# V1.net
KiCad netlist of a schematic drawn in Altium Designer
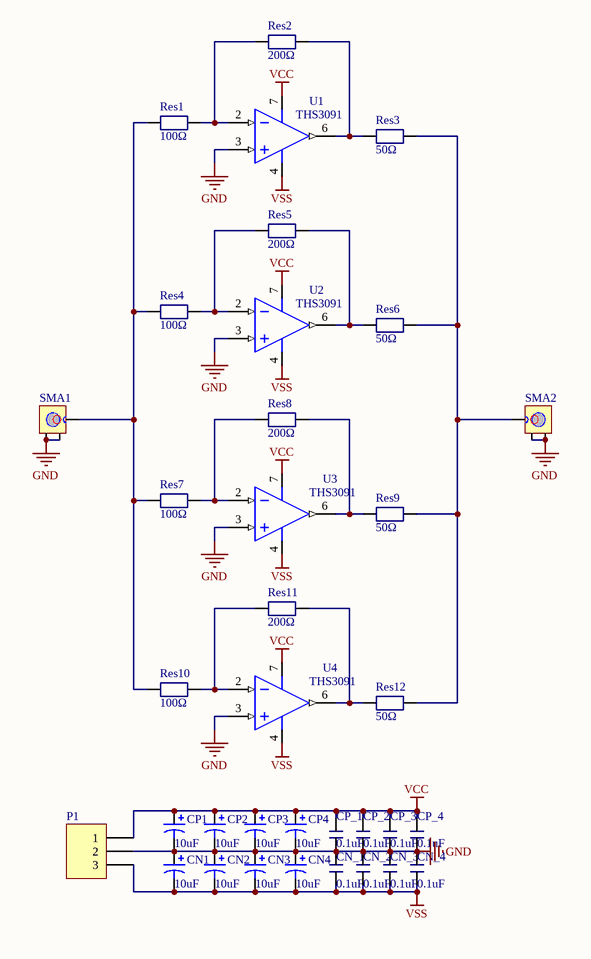
[diagram p0: V1.SchDoc]

(export (version "E")
  (design (tool "Eeschema 10.0.6"))
  (components
    (comp (ref "CN1")
      (value "10uF")
      (footprint "CAP_BTAN")
      (description "Polarized Capacitor (Radial)")
      (fields (field (name "Comment") "Cap Pol1") (field (name "PUBLISHER") "Altium Limited"))
      (libsource (lib "Miscellaneous Devices") (part "Cap Pol1"))
    )
    (comp (ref "CN2")
      (value "10uF")
      (footprint "CAP_BTAN")
      (description "Polarized Capacitor (Radial)")
      (fields (field (name "Comment") "Cap Pol1") (field (name "PUBLISHER") "Altium Limited"))
      (libsource (lib "Miscellaneous Devices") (part "Cap Pol1"))
    )
    (comp (ref "CN3")
      (value "10uF")
      (footprint "CAP_BTAN")
      (description "Polarized Capacitor (Radial)")
      (fields (field (name "Comment") "Cap Pol1") (field (name "PUBLISHER") "Altium Limited"))
      (libsource (lib "Miscellaneous Devices") (part "Cap Pol1"))
    )
    (comp (ref "CN4")
      (value "10uF")
      (footprint "CAP_BTAN")
      (description "Polarized Capacitor (Radial)")
      (fields (field (name "Comment") "Cap Pol1") (field (name "PUBLISHER") "Altium Limited"))
      (libsource (lib "Miscellaneous Devices") (part "Cap Pol1"))
    )
    (comp (ref "CN_1")
      (value "0.1uF")
      (footprint "C0805")
      (description "贴片电容")
      (fields (field (name "Comment") "cap"))
      (libsource (lib "Fengyie") (part "cap"))
    )
    (comp (ref "CN_2")
      (value "0.1uF")
      (footprint "C0805")
      (description "贴片电容")
      (fields (field (name "Comment") "cap"))
      (libsource (lib "Fengyie") (part "cap"))
    )
    (comp (ref "CN_3")
      (value "0.1uF")
      (footprint "C0805")
      (description "贴片电容")
      (fields (field (name "Comment") "cap"))
      (libsource (lib "Fengyie") (part "cap"))
    )
    (comp (ref "CN_4")
      (value "0.1uF")
      (footprint "C0805")
      (description "贴片电容")
      (fields (field (name "Comment") "cap"))
      (libsource (lib "Fengyie") (part "cap"))
    )
    (comp (ref "CP1")
      (value "10uF")
      (footprint "CAP_BTAN")
      (description "Polarized Capacitor (Radial)")
      (fields (field (name "Comment") "Cap Pol1") (field (name "PUBLISHER") "Altium Limited"))
      (libsource (lib "Miscellaneous Devices") (part "Cap Pol1"))
    )
    (comp (ref "CP2")
      (value "10uF")
      (footprint "CAP_BTAN")
      (description "Polarized Capacitor (Radial)")
      (fields (field (name "Comment") "Cap Pol1") (field (name "PUBLISHER") "Altium Limited"))
      (libsource (lib "Miscellaneous Devices") (part "Cap Pol1"))
    )
    (comp (ref "CP3")
      (value "10uF")
      (footprint "CAP_BTAN")
      (description "Polarized Capacitor (Radial)")
      (fields (field (name "Comment") "Cap Pol1") (field (name "PUBLISHER") "Altium Limited"))
      (libsource (lib "Miscellaneous Devices") (part "Cap Pol1"))
    )
    (comp (ref "CP4")
      (value "10uF")
      (footprint "CAP_BTAN")
      (description "Polarized Capacitor (Radial)")
      (fields (field (name "Comment") "Cap Pol1") (field (name "PUBLISHER") "Altium Limited"))
      (libsource (lib "Miscellaneous Devices") (part "Cap Pol1"))
    )
    (comp (ref "CP_1")
      (value "0.1uF")
      (footprint "C0805")
      (description "贴片电容")
      (fields (field (name "Comment") "cap"))
      (libsource (lib "Fengyie") (part "cap"))
    )
    (comp (ref "CP_2")
      (value "0.1uF")
      (footprint "C0805")
      (description "贴片电容")
      (fields (field (name "Comment") "cap"))
      (libsource (lib "Fengyie") (part "cap"))
    )
    (comp (ref "CP_3")
      (value "0.1uF")
      (footprint "C0805")
      (description "贴片电容")
      (fields (field (name "Comment") "cap"))
      (libsource (lib "Fengyie") (part "cap"))
    )
    (comp (ref "CP_4")
      (value "0.1uF")
      (footprint "C0805")
      (description "贴片电容")
      (fields (field (name "Comment") "cap"))
      (libsource (lib "Fengyie") (part "cap"))
    )
    (comp (ref "P1")
      (value "Header 3")
      (footprint "HDR1X3")
      (description "Header, 3-Pin")
      (fields (field (name "PUBLISHER") "Altium Limited"))
      (libsource (lib "Miscellaneous Connectors") (part "Header 3"))
    )
    (comp (ref "Res1")
      (value "100Ω")
      (footprint "C0805")
      (description "适用于0805的贴片元件，包括磁珠")
      (fields (field (name "Comment") "Res"))
      (libsource (lib "Fengyie") (part "Res"))
    )
    (comp (ref "Res2")
      (value "200Ω")
      (footprint "R-AXIAL0.3")
      (description "适用于0805的贴片元件，包括磁珠")
      (fields (field (name "Comment") "Res"))
      (libsource (lib "Fengyie") (part "Res"))
    )
    (comp (ref "Res3")
      (value "50Ω")
      (footprint "C0805")
      (description "适用于0805的贴片元件，包括磁珠")
      (fields (field (name "Comment") "Res"))
      (libsource (lib "Fengyie") (part "Res"))
    )
    (comp (ref "Res4")
      (value "100Ω")
      (footprint "C0805")
      (description "适用于0805的贴片元件，包括磁珠")
      (fields (field (name "Comment") "Res"))
      (libsource (lib "Fengyie") (part "Res"))
    )
    (comp (ref "Res5")
      (value "200Ω")
      (footprint "R-AXIAL0.3")
      (description "适用于0805的贴片元件，包括磁珠")
      (fields (field (name "Comment") "Res"))
      (libsource (lib "Fengyie") (part "Res"))
    )
    (comp (ref "Res6")
      (value "50Ω")
      (footprint "C0805")
      (description "适用于0805的贴片元件，包括磁珠")
      (fields (field (name "Comment") "Res"))
      (libsource (lib "Fengyie") (part "Res"))
    )
    (comp (ref "Res7")
      (value "100Ω")
      (footprint "C0805")
      (description "适用于0805的贴片元件，包括磁珠")
      (fields (field (name "Comment") "Res"))
      (libsource (lib "Fengyie") (part "Res"))
    )
    (comp (ref "Res8")
      (value "200Ω")
      (footprint "R-AXIAL0.3")
      (description "适用于0805的贴片元件，包括磁珠")
      (fields (field (name "Comment") "Res"))
      (libsource (lib "Fengyie") (part "Res"))
    )
    (comp (ref "Res9")
      (value "50Ω")
      (footprint "C0805")
      (description "适用于0805的贴片元件，包括磁珠")
      (fields (field (name "Comment") "Res"))
      (libsource (lib "Fengyie") (part "Res"))
    )
    (comp (ref "Res10")
      (value "100Ω")
      (footprint "C0805")
      (description "适用于0805的贴片元件，包括磁珠")
      (fields (field (name "Comment") "Res"))
      (libsource (lib "Fengyie") (part "Res"))
    )
    (comp (ref "Res11")
      (value "200Ω")
      (footprint "R-AXIAL0.3")
      (description "适用于0805的贴片元件，包括磁珠")
      (fields (field (name "Comment") "Res"))
      (libsource (lib "Fengyie") (part "Res"))
    )
    (comp (ref "Res12")
      (value "50Ω")
      (footprint "C0805")
      (description "适用于0805的贴片元件，包括磁珠")
      (fields (field (name "Comment") "Res"))
      (libsource (lib "Fengyie") (part "Res"))
    )
    (comp (ref "SMA1")
      (value "SMA-xie")
      (footprint "sma-xie")
      (description "外螺内孔，斜角，或直四角斜着放置")
      (libsource (lib "Fengyie") (part "SMA-xie"))
    )
    (comp (ref "SMA2")
      (value "SMA-xie")
      (footprint "sma-xie")
      (description "外螺内孔，斜角，或直四角斜着放置")
      (libsource (lib "") (part "SMA-xie_1"))
    )
    (comp (ref "U1")
      (value "THS3091")
      (footprint "SOIC-8D")
      (description "单路高压低失真电流反馈 运放 ,通常申请DDA，即下方带有热焊盘的，有利于散热")
      (libsource (lib "Fengyie") (part "THS3091"))
    )
    (comp (ref "U2")
      (value "THS3091")
      (footprint "SOIC-8D")
      (description "单路高压低失真电流反馈 运放 ,通常申请DDA，即下方带有热焊盘的，有利于散热")
      (libsource (lib "Fengyie") (part "THS3091"))
    )
    (comp (ref "U3")
      (value "THS3091")
      (footprint "SOIC-8D")
      (description "单路高压低失真电流反馈 运放 ,通常申请DDA，即下方带有热焊盘的，有利于散热")
      (libsource (lib "Fengyie") (part "THS3091"))
    )
    (comp (ref "U4")
      (value "THS3091")
      (footprint "SOIC-8D")
      (description "单路高压低失真电流反馈 运放 ,通常申请DDA，即下方带有热焊盘的，有利于散热")
      (libsource (lib "Fengyie") (part "THS3091"))
    )
  )
  (nets
    (net (code "1") (name "GND") (class "Default")
      (node (ref "CN1") (pin "1") (pinfunction "1_1") (pintype "passive"))
      (node (ref "CN2") (pin "1") (pinfunction "1_1") (pintype "passive"))
      (node (ref "CN3") (pin "1") (pinfunction "1_1") (pintype "passive"))
      (node (ref "CN4") (pin "1") (pinfunction "1_1") (pintype "passive"))
      (node (ref "CN_1") (pin "1") (pinfunction "1_1") (pintype "passive"))
      (node (ref "CN_2") (pin "1") (pinfunction "1_1") (pintype "passive"))
      (node (ref "CN_3") (pin "1") (pinfunction "1_1") (pintype "passive"))
      (node (ref "CN_4") (pin "1") (pinfunction "1_1") (pintype "passive"))
      (node (ref "CP1") (pin "2") (pinfunction "2_2") (pintype "passive"))
      (node (ref "CP2") (pin "2") (pinfunction "2_2") (pintype "passive"))
      (node (ref "CP3") (pin "2") (pinfunction "2_2") (pintype "passive"))
      (node (ref "CP4") (pin "2") (pinfunction "2_2") (pintype "passive"))
      (node (ref "CP_1") (pin "2") (pinfunction "2_2") (pintype "passive"))
      (node (ref "CP_2") (pin "2") (pinfunction "2_2") (pintype "passive"))
      (node (ref "CP_3") (pin "2") (pinfunction "2_2") (pintype "passive"))
      (node (ref "CP_4") (pin "2") (pinfunction "2_2") (pintype "passive"))
      (node (ref "P1") (pin "2") (pinfunction "2_2") (pintype "passive"))
      (node (ref "SMA1") (pin "1") (pinfunction "gnd_1") (pintype "passive"))
      (node (ref "SMA1") (pin "3") (pinfunction "gnd_3") (pintype "passive"))
      (node (ref "SMA2") (pin "1") (pinfunction "gnd_1") (pintype "passive"))
      (node (ref "SMA2") (pin "3") (pinfunction "gnd_3") (pintype "passive"))
      (node (ref "U1") (pin "3") (pinfunction "IN+_3") (pintype "input"))
      (node (ref "U2") (pin "3") (pinfunction "IN+_3") (pintype "input"))
      (node (ref "U3") (pin "3") (pinfunction "IN+_3") (pintype "input"))
      (node (ref "U4") (pin "3") (pinfunction "IN+_3") (pintype "input"))
    )
    (net (code "2") (name "Net-(SMA1-signal)") (class "Default")
      (node (ref "Res1") (pin "1") (pinfunction "1_1") (pintype "passive"))
      (node (ref "Res10") (pin "1") (pinfunction "1_1") (pintype "passive"))
      (node (ref "Res4") (pin "1") (pinfunction "1_1") (pintype "passive"))
      (node (ref "Res7") (pin "1") (pinfunction "1_1") (pintype "passive"))
      (node (ref "SMA1") (pin "2") (pinfunction "signal_2") (pintype "passive"))
    )
    (net (code "3") (name "Net-(SMA2-signal)") (class "Default")
      (node (ref "Res12") (pin "2") (pinfunction "2_2") (pintype "passive"))
      (node (ref "Res3") (pin "2") (pinfunction "2_2") (pintype "passive"))
      (node (ref "Res6") (pin "2") (pinfunction "2_2") (pintype "passive"))
      (node (ref "Res9") (pin "2") (pinfunction "2_2") (pintype "passive"))
      (node (ref "SMA2") (pin "2") (pinfunction "signal_2") (pintype "passive"))
    )
    (net (code "4") (name "Net-(U1-IN-)") (class "Default")
      (node (ref "Res1") (pin "2") (pinfunction "2_2") (pintype "passive"))
      (node (ref "Res2") (pin "1") (pinfunction "1_1") (pintype "passive"))
      (node (ref "U1") (pin "2") (pinfunction "IN-_2") (pintype "input"))
    )
    (net (code "5") (name "Net-(U1-OUT)") (class "Default")
      (node (ref "Res2") (pin "2") (pinfunction "2_2") (pintype "passive"))
      (node (ref "Res3") (pin "1") (pinfunction "1_1") (pintype "passive"))
      (node (ref "U1") (pin "6") (pinfunction "OUT_6") (pintype "output"))
    )
    (net (code "6") (name "Net-(U2-IN-)") (class "Default")
      (node (ref "Res4") (pin "2") (pinfunction "2_2") (pintype "passive"))
      (node (ref "Res5") (pin "1") (pinfunction "1_1") (pintype "passive"))
      (node (ref "U2") (pin "2") (pinfunction "IN-_2") (pintype "input"))
    )
    (net (code "7") (name "Net-(U2-OUT)") (class "Default")
      (node (ref "Res5") (pin "2") (pinfunction "2_2") (pintype "passive"))
      (node (ref "Res6") (pin "1") (pinfunction "1_1") (pintype "passive"))
      (node (ref "U2") (pin "6") (pinfunction "OUT_6") (pintype "output"))
    )
    (net (code "8") (name "Net-(U3-IN-)") (class "Default")
      (node (ref "Res7") (pin "2") (pinfunction "2_2") (pintype "passive"))
      (node (ref "Res8") (pin "1") (pinfunction "1_1") (pintype "passive"))
      (node (ref "U3") (pin "2") (pinfunction "IN-_2") (pintype "input"))
    )
    (net (code "9") (name "Net-(U3-OUT)") (class "Default")
      (node (ref "Res8") (pin "2") (pinfunction "2_2") (pintype "passive"))
      (node (ref "Res9") (pin "1") (pinfunction "1_1") (pintype "passive"))
      (node (ref "U3") (pin "6") (pinfunction "OUT_6") (pintype "output"))
    )
    (net (code "10") (name "Net-(U4-IN-)") (class "Default")
      (node (ref "Res10") (pin "2") (pinfunction "2_2") (pintype "passive"))
      (node (ref "Res11") (pin "1") (pinfunction "1_1") (pintype "passive"))
      (node (ref "U4") (pin "2") (pinfunction "IN-_2") (pintype "input"))
    )
    (net (code "11") (name "Net-(U4-OUT)") (class "Default")
      (node (ref "Res11") (pin "2") (pinfunction "2_2") (pintype "passive"))
      (node (ref "Res12") (pin "1") (pinfunction "1_1") (pintype "passive"))
      (node (ref "U4") (pin "6") (pinfunction "OUT_6") (pintype "output"))
    )
    (net (code "12") (name "VCC") (class "Default")
      (node (ref "CP1") (pin "1") (pinfunction "1_1") (pintype "passive"))
      (node (ref "CP2") (pin "1") (pinfunction "1_1") (pintype "passive"))
      (node (ref "CP3") (pin "1") (pinfunction "1_1") (pintype "passive"))
      (node (ref "CP4") (pin "1") (pinfunction "1_1") (pintype "passive"))
      (node (ref "CP_1") (pin "1") (pinfunction "1_1") (pintype "passive"))
      (node (ref "CP_2") (pin "1") (pinfunction "1_1") (pintype "passive"))
      (node (ref "CP_3") (pin "1") (pinfunction "1_1") (pintype "passive"))
      (node (ref "CP_4") (pin "1") (pinfunction "1_1") (pintype "passive"))
      (node (ref "P1") (pin "1") (pinfunction "1_1") (pintype "passive"))
      (node (ref "U1") (pin "7") (pinfunction "V+_7") (pintype "power_in"))
      (node (ref "U2") (pin "7") (pinfunction "V+_7") (pintype "power_in"))
      (node (ref "U3") (pin "7") (pinfunction "V+_7") (pintype "power_in"))
      (node (ref "U4") (pin "7") (pinfunction "V+_7") (pintype "power_in"))
    )
    (net (code "13") (name "VSS") (class "Default")
      (node (ref "CN1") (pin "2") (pinfunction "2_2") (pintype "passive"))
      (node (ref "CN2") (pin "2") (pinfunction "2_2") (pintype "passive"))
      (node (ref "CN3") (pin "2") (pinfunction "2_2") (pintype "passive"))
      (node (ref "CN4") (pin "2") (pinfunction "2_2") (pintype "passive"))
      (node (ref "CN_1") (pin "2") (pinfunction "2_2") (pintype "passive"))
      (node (ref "CN_2") (pin "2") (pinfunction "2_2") (pintype "passive"))
      (node (ref "CN_3") (pin "2") (pinfunction "2_2") (pintype "passive"))
      (node (ref "CN_4") (pin "2") (pinfunction "2_2") (pintype "passive"))
      (node (ref "P1") (pin "3") (pinfunction "3_3") (pintype "passive"))
      (node (ref "U1") (pin "4") (pinfunction "V-_4") (pintype "power_in"))
      (node (ref "U2") (pin "4") (pinfunction "V-_4") (pintype "power_in"))
      (node (ref "U3") (pin "4") (pinfunction "V-_4") (pintype "power_in"))
      (node (ref "U4") (pin "4") (pinfunction "V-_4") (pintype "power_in"))
    )
  )
)
